# Sh1_MPU.net
KiCad netlist of a schematic drawn in Altium Designer
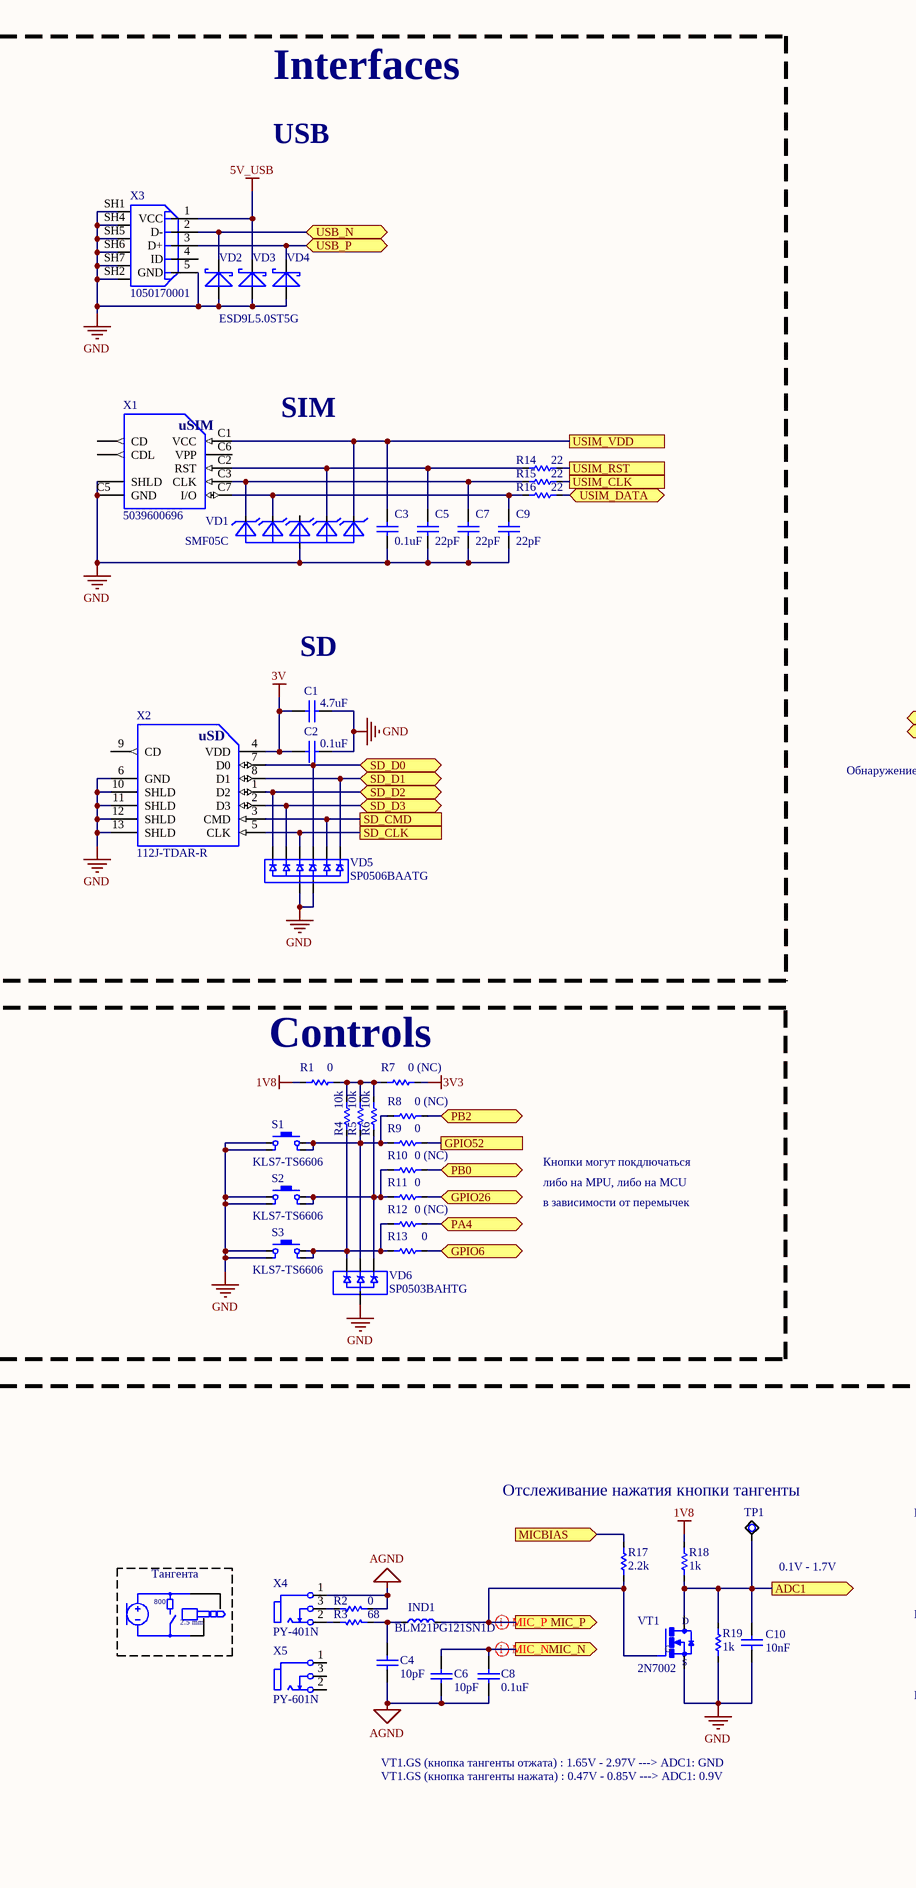
[diagram p0: Sh1_MPU.SchDoc, left]
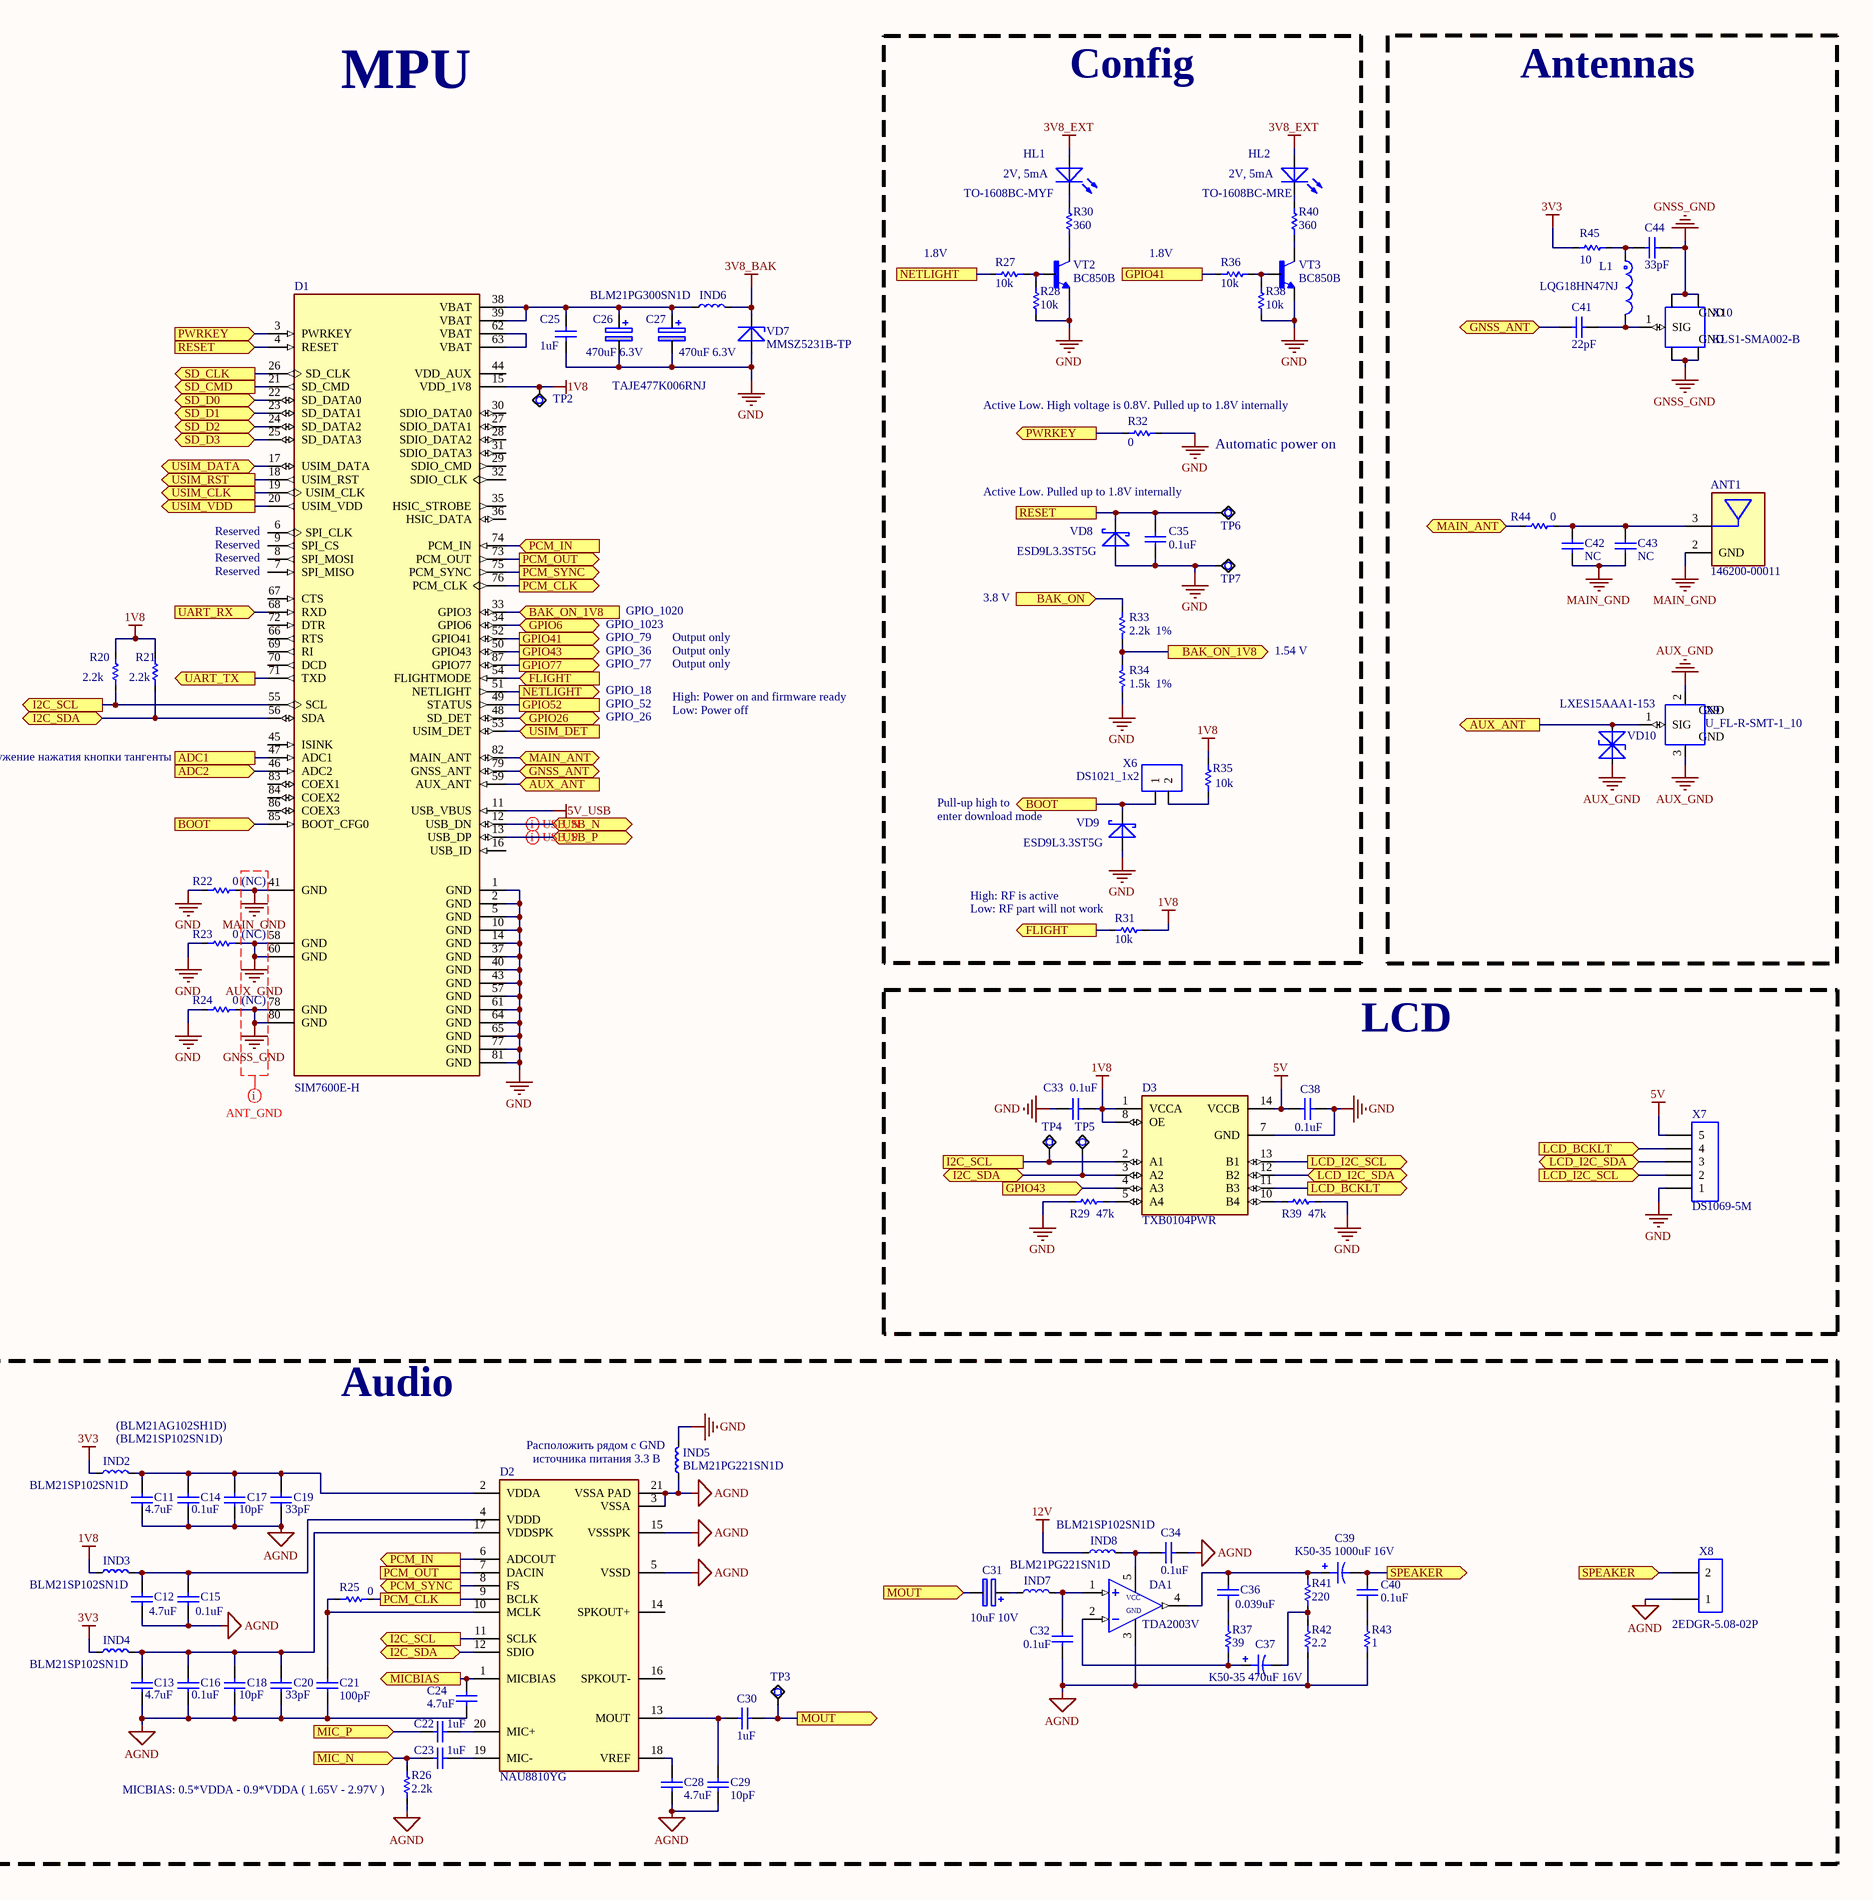
[diagram p1: Sh1_MPU.SchDoc, right]

(export (version "E")
  (design (tool "Eeschema 10.0.6"))
  (components
    (comp (ref "ANT1")
      (value "146200-00011")
      (footprint "Molex_146200-0011_MFG")
      (description "LTE Cellular Ceramic Antenna 698MHz-2.7GHz , SMT")
      (libsource (lib "MyCompLib") (part "146200-0001(11)"))
    )
    (comp (ref "C1")
      (value "4.7uF")
      (footprint "C_SMD0603")
      (description "0603 SMD Capacitor")
      (libsource (lib "") (part "C_SMD_1"))
    )
    (comp (ref "C2")
      (value "0.1uF")
      (footprint "C_SMD0603")
      (description "0603 SMD Capacitor")
      (libsource (lib "") (part "C_SMD_1"))
    )
    (comp (ref "C3")
      (value "0.1uF")
      (footprint "C_SMD0603")
      (description "0603 SMD Capacitor")
      (libsource (lib "") (part "C_SMD_1"))
    )
    (comp (ref "C4")
      (value "10pF")
      (footprint "C_SMD0603")
      (description "0603 SMD Capacitor")
      (libsource (lib "MyCompLib") (part "C_SMD"))
    )
    (comp (ref "C5")
      (value "22pF")
      (footprint "C_SMD0603")
      (description "0603 SMD Capacitor")
      (libsource (lib "") (part "C_SMD_1"))
    )
    (comp (ref "C6")
      (value "10pF")
      (footprint "C_SMD0603")
      (description "0603 SMD Capacitor")
      (libsource (lib "MyCompLib") (part "C_SMD"))
    )
    (comp (ref "C7")
      (value "22pF")
      (footprint "C_SMD0603")
      (description "0603 SMD Capacitor")
      (libsource (lib "") (part "C_SMD_1"))
    )
    (comp (ref "C8")
      (value "0.1uF")
      (footprint "C_SMD0603")
      (description "0603 SMD Capacitor")
      (libsource (lib "MyCompLib") (part "C_SMD"))
    )
    (comp (ref "C9")
      (value "22pF")
      (footprint "C_SMD0603")
      (description "0603 SMD Capacitor")
      (libsource (lib "") (part "C_SMD_1"))
    )
    (comp (ref "C10")
      (value "10nF")
      (footprint "C_SMD0603")
      (description "0603 SMD Capacitor")
      (libsource (lib "MyCompLib") (part "C_SMD"))
    )
    (comp (ref "C11")
      (value "4.7uF")
      (footprint "C_SMD0603")
      (description "0603 SMD Capacitor")
      (libsource (lib "MyCompLib") (part "C_SMD"))
    )
    (comp (ref "C12")
      (value "4.7uF")
      (footprint "C_SMD0603")
      (description "0603 SMD Capacitor")
      (libsource (lib "MyCompLib") (part "C_SMD"))
    )
    (comp (ref "C13")
      (value "4.7uF")
      (footprint "C_SMD0603")
      (description "0603 SMD Capacitor")
      (libsource (lib "MyCompLib") (part "C_SMD"))
    )
    (comp (ref "C14")
      (value "0.1uF")
      (footprint "C_SMD0603")
      (description "0603 SMD Capacitor")
      (libsource (lib "MyCompLib") (part "C_SMD"))
    )
    (comp (ref "C15")
      (value "0.1uF")
      (footprint "C_SMD0603")
      (description "0603 SMD Capacitor")
      (libsource (lib "MyCompLib") (part "C_SMD"))
    )
    (comp (ref "C16")
      (value "0.1uF")
      (footprint "C_SMD0603")
      (description "0603 SMD Capacitor")
      (libsource (lib "MyCompLib") (part "C_SMD"))
    )
    (comp (ref "C17")
      (value "10pF")
      (footprint "C_SMD0603")
      (description "0603 SMD Capacitor")
      (libsource (lib "MyCompLib") (part "C_SMD"))
    )
    (comp (ref "C18")
      (value "10pF")
      (footprint "C_SMD0603")
      (description "0603 SMD Capacitor")
      (libsource (lib "MyCompLib") (part "C_SMD"))
    )
    (comp (ref "C19")
      (value "33pF")
      (footprint "C_SMD0603")
      (description "0603 SMD Capacitor")
      (libsource (lib "MyCompLib") (part "C_SMD"))
    )
    (comp (ref "C20")
      (value "33pF")
      (footprint "C_SMD0603")
      (description "0603 SMD Capacitor")
      (libsource (lib "MyCompLib") (part "C_SMD"))
    )
    (comp (ref "C21")
      (value "100pF")
      (footprint "C_SMD0603")
      (description "0603 SMD Capacitor")
      (libsource (lib "MyCompLib") (part "C_SMD"))
    )
    (comp (ref "C22")
      (value "1uF")
      (footprint "C_SMD0603")
      (description "0603 SMD Capacitor")
      (libsource (lib "MyCompLib") (part "C_SMD"))
    )
    (comp (ref "C23")
      (value "1uF")
      (footprint "C_SMD0603")
      (description "0603 SMD Capacitor")
      (libsource (lib "MyCompLib") (part "C_SMD"))
    )
    (comp (ref "C24")
      (value "4.7uF")
      (footprint "C_SMD0603")
      (description "0603 SMD Capacitor")
      (libsource (lib "MyCompLib") (part "C_SMD"))
    )
    (comp (ref "C25")
      (value "1uF")
      (footprint "C_SMD0603")
      (description "0603 SMD Capacitor")
      (libsource (lib "MyCompLib") (part "C_SMD"))
    )
    (comp (ref "C26")
      (value "470uF 6.3V")
      (footprint "TECAP_E")
      (description "Конденсатор танталовый SMD тип Е")
      (libsource (lib "MyCompLib") (part "C_SMD_Tantalum"))
    )
    (comp (ref "C27")
      (value "470uF 6.3V")
      (footprint "TECAP_E")
      (description "Конденсатор танталовый SMD тип Е")
      (libsource (lib "MyCompLib") (part "C_SMD_Tantalum"))
    )
    (comp (ref "C28")
      (value "4.7uF")
      (footprint "C_SMD0603")
      (description "0603 SMD Capacitor")
      (libsource (lib "MyCompLib") (part "C_SMD"))
    )
    (comp (ref "C29")
      (value "10pF")
      (footprint "C_SMD0603")
      (description "0603 SMD Capacitor")
      (libsource (lib "MyCompLib") (part "C_SMD"))
    )
    (comp (ref "C30")
      (value "1uF")
      (footprint "C_SMD1206")
      (description "1206 SMD Capacitor")
      (libsource (lib "MyCompLib") (part "C_SMD"))
    )
    (comp (ref "C31")
      (value "10uF 10V")
      (footprint "TECAP_B")
      (description "Конденсатор танталовый SMD 10uF 10V тип B")
      (libsource (lib "") (part "C_SMD_Tantalum_1"))
    )
    (comp (ref "C32")
      (value "0.1uF")
      (footprint "C_SMD0603")
      (description "0603 SMD Capacitor")
      (libsource (lib "MyCompLib") (part "C_SMD"))
    )
    (comp (ref "C33")
      (value "0.1uF")
      (footprint "C_SMD0603")
      (description "0603 SMD Capacitor")
      (libsource (lib "MyCompLib") (part "C_SMD"))
    )
    (comp (ref "C34")
      (value "0.1uF")
      (footprint "C_SMD0603")
      (description "0603 SMD Capacitor")
      (libsource (lib "MyCompLib") (part "C_SMD"))
    )
    (comp (ref "C35")
      (value "0.1uF")
      (footprint "C_SMD0603")
      (description "0603 SMD Capacitor")
      (libsource (lib "MyCompLib") (part "C_SMD"))
    )
    (comp (ref "C36")
      (value "0.039uF")
      (footprint "C_SMD0603")
      (description "0603 SMD Capacitor")
      (libsource (lib "MyCompLib") (part "C_SMD"))
    )
    (comp (ref "C37")
      (value "K50-35 470uF 16V")
      (footprint "K50-35 8x11.5x3.5")
      (description "Конденсатор электролитический алюминиевый 470мкФ, 16В")
      (libsource (lib "MyCompLib") (part "K50-35"))
    )
    (comp (ref "C38")
      (value "0.1uF")
      (footprint "C_SMD0603")
      (description "0603 SMD Capacitor")
      (libsource (lib "MyCompLib") (part "C_SMD"))
    )
    (comp (ref "C39")
      (value "K50-35 1000uF 16V")
      (footprint "K50-35 10x12.5x5")
      (description "Конденсатор электролитический алюминиевый 1000мкФ, 16В")
      (libsource (lib "MyCompLib") (part "K50-35"))
    )
    (comp (ref "C40")
      (value "0.1uF")
      (footprint "C_SMD0603")
      (description "0603 SMD Capacitor")
      (libsource (lib "MyCompLib") (part "C_SMD"))
    )
    (comp (ref "C41")
      (value "22pF")
      (footprint "C_SMD0805")
      (description "0805 SMD Capacitor")
      (libsource (lib "MyCompLib") (part "C_SMD"))
    )
    (comp (ref "C42")
      (value "NС")
      (footprint "C_SMD0603")
      (description "0603 SMD Capacitor")
      (libsource (lib "MyCompLib") (part "C_SMD"))
    )
    (comp (ref "C43")
      (value "NС")
      (footprint "C_SMD0603")
      (description "0603 SMD Capacitor")
      (libsource (lib "MyCompLib") (part "C_SMD"))
    )
    (comp (ref "C44")
      (value "33pF")
      (footprint "C_SMD0603")
      (description "0603 SMD Capacitor")
      (libsource (lib "MyCompLib") (part "C_SMD"))
    )
    (comp (ref "D1")
      (value "SIM7600E-H")
      (footprint "IC_SIM7600E-H")
      (description "Multi-Band LTE-TDD/LTE-FDD/HSPA+ and GSM/GPRS/EDGE module")
      (fields (field (name "MF") "Simcom"))
      (libsource (lib "MyCompLib") (part "SIM7600E-H"))
    )
    (comp (ref "D2")
      (value "NAU8810YG")
      (footprint "NAU8810YG")
      (description "AUDIO CODEC MONO 20QFN")
      (fields (field (name "VOLTAGE") "3.6V") (field (name "MANUFACTURER") "Nuvoton Technology Corporation"))
      (libsource (lib "MyCompLib") (part "NAU8810YG"))
    )
    (comp (ref "D3")
      (value "TXB0104PWR")
      (footprint "SOP65P640X120-14N")
      (fields (field (name "MF") "Texas Instruments"))
      (libsource (lib "MyCompLib") (part "TXB0104PWR"))
    )
    (comp (ref "DA1")
      (value "TDA2003V")
      (footprint "TDA2003V _HS-117-30 (ABM-161-30)")
      (description "Amplifier IC 1-Channel _Mono_ Class AB 5-PENTAWATT 10W")
      (fields (field (name "MF") "STMicroelectronics"))
      (libsource (lib "MyCompLib") (part "TDA2003V"))
    )
    (comp (ref "HL1")
      (value "TO-1608BC-MYF")
      (footprint "LED_SMD1608 + THR0254")
      (description "Vf =2 V, 20mA, 0603\r\n\r\nTO-1608BC-BF \\  TO-1608BC-MRE")
      (libsource (lib "MyCompLib") (part "LED_SMD"))
    )
    (comp (ref "HL2")
      (value "TO-1608BC-MRE")
      (footprint "LED_SMD1608 + THR0254")
      (description "Vf =2 V, 20mA, 0603\r\n\r\nTO-1608BC-BF \\  TO-1608BC-MRE")
      (libsource (lib "MyCompLib") (part "LED_SMD"))
    )
    (comp (ref "IND1")
      (value "BLM21PG121SN1D")
      (footprint "BLM21PG221_0805")
      (description "0805, Дроссель подавления ЭМП 120Ohm 25% 100MHz 3A")
      (libsource (lib "") (part "BLM21PG221SN1D_1"))
    )
    (comp (ref "IND2")
      (value "BLM21SP102SN1D")
      (footprint "BLM21PG221_0805")
      (description "0805, Дроссель подавления ЭМП 1KOhm 25% 100MHz 1.6A 0.12Ohm")
      (libsource (lib "MyCompLib") (part "BLM21PG221SN1D"))
    )
    (comp (ref "IND3")
      (value "BLM21SP102SN1D")
      (footprint "BLM21PG221_0805")
      (description "0805, Дроссель подавления ЭМП 1KOhm 25% 100MHz 1.6A 0.12Ohm")
      (libsource (lib "MyCompLib") (part "BLM21PG221SN1D"))
    )
    (comp (ref "IND4")
      (value "BLM21SP102SN1D")
      (footprint "BLM21PG221_0805")
      (description "0805, Дроссель подавления ЭМП 1KOhm 25% 100MHz 1.6A 0.12Ohm")
      (libsource (lib "MyCompLib") (part "BLM21PG221SN1D"))
    )
    (comp (ref "IND5")
      (value "BLM21PG221SN1D")
      (footprint "BLM21PG221_0805")
      (description "0805, Дроссель подавления ЭМП 220Ohm +25% 100MHz 2A 45mOhm")
      (libsource (lib "MyCompLib") (part "BLM21PG221SN1D"))
    )
    (comp (ref "IND6")
      (value "BLM21PG300SN1D")
      (footprint "BLM21PG221_0805")
      (description "0805, Дроссель подавления ЭМП 100МГц:30Ом; 3А")
      (libsource (lib "MyCompLib") (part "BLM21PG221SN1D"))
    )
    (comp (ref "IND7")
      (value "BLM21PG221SN1D")
      (footprint "BLM21PG221_0805")
      (description "0805, Дроссель подавления ЭМП 220Ohm +25% 100MHz 2A 45mOhm")
      (libsource (lib "MyCompLib") (part "BLM21PG221SN1D"))
    )
    (comp (ref "IND8")
      (value "BLM21SP102SN1D")
      (footprint "BLM21PG221_0805")
      (description "0805, Дроссель подавления ЭМП 1KOhm 25% 100MHz 1.6A 0.12Ohm")
      (libsource (lib "MyCompLib") (part "BLM21PG221SN1D"))
    )
    (comp (ref "L1")
      (value "LQG18HN47NJ")
      (footprint "L0603")
      (libsource (lib "MyCompLib") (part "LQG18HN47NJ"))
    )
    (comp (ref "R1")
      (value "0")
      (footprint "R_SMD0603")
      (description "0603 SMD Resistor")
      (libsource (lib "MyCompLib") (part "R_SMD"))
    )
    (comp (ref "R2")
      (value "0")
      (footprint "R_SMD0603")
      (description "0603 SMD Resistor")
      (libsource (lib "MyCompLib") (part "R_SMD"))
    )
    (comp (ref "R3")
      (value "68")
      (footprint "R_SMD0603")
      (description "0603 SMD Resistor")
      (libsource (lib "MyCompLib") (part "R_SMD"))
    )
    (comp (ref "R4")
      (value "10k")
      (footprint "R_SMD0603")
      (description "0603 SMD Resistor")
      (libsource (lib "MyCompLib") (part "R_SMD"))
    )
    (comp (ref "R5")
      (value "10k")
      (footprint "R_SMD0603")
      (description "0603 SMD Resistor")
      (libsource (lib "MyCompLib") (part "R_SMD"))
    )
    (comp (ref "R6")
      (value "10k")
      (footprint "R_SMD0603")
      (description "0603 SMD Resistor")
      (libsource (lib "MyCompLib") (part "R_SMD"))
    )
    (comp (ref "R7")
      (value "0 (NC)")
      (footprint "R_SMD0603")
      (description "0603 SMD Resistor")
      (libsource (lib "MyCompLib") (part "R_SMD"))
    )
    (comp (ref "R8")
      (value "0 (NC)")
      (footprint "R_SMD0603")
      (description "0603 SMD Resistor")
      (libsource (lib "MyCompLib") (part "R_SMD"))
    )
    (comp (ref "R9")
      (value "0")
      (footprint "R_SMD0603")
      (description "0603 SMD Resistor")
      (libsource (lib "MyCompLib") (part "R_SMD"))
    )
    (comp (ref "R10")
      (value "0 (NC)")
      (footprint "R_SMD0603")
      (description "0603 SMD Resistor")
      (libsource (lib "MyCompLib") (part "R_SMD"))
    )
    (comp (ref "R11")
      (value "0")
      (footprint "R_SMD0603")
      (description "0603 SMD Resistor")
      (libsource (lib "MyCompLib") (part "R_SMD"))
    )
    (comp (ref "R12")
      (value "0 (NC)")
      (footprint "R_SMD0603")
      (description "0603 SMD Resistor")
      (libsource (lib "MyCompLib") (part "R_SMD"))
    )
    (comp (ref "R13")
      (value "0")
      (footprint "R_SMD0603")
      (description "0603 SMD Resistor")
      (libsource (lib "MyCompLib") (part "R_SMD"))
    )
    (comp (ref "R14")
      (value "22")
      (footprint "R_SMD0603")
      (description "0603 SMD Resistor")
      (libsource (lib "MyCompLib") (part "R_SMD"))
    )
    (comp (ref "R15")
      (value "22")
      (footprint "R_SMD0603")
      (description "0603 SMD Resistor")
      (libsource (lib "MyCompLib") (part "R_SMD"))
    )
    (comp (ref "R16")
      (value "22")
      (footprint "R_SMD0603")
      (description "0603 SMD Resistor")
      (libsource (lib "MyCompLib") (part "R_SMD"))
    )
    (comp (ref "R17")
      (value "2.2k")
      (footprint "R_SMD0603")
      (description "0603 SMD Resistor")
      (libsource (lib "MyCompLib") (part "R_SMD"))
    )
    (comp (ref "R18")
      (value "1k")
      (footprint "R_SMD0603")
      (description "0603 SMD Resistor")
      (libsource (lib "MyCompLib") (part "R_SMD"))
    )
    (comp (ref "R19")
      (value "1k")
      (footprint "R_SMD0603")
      (description "0603 SMD Resistor")
      (libsource (lib "MyCompLib") (part "R_SMD"))
    )
    (comp (ref "R20")
      (value "2.2k")
      (footprint "R_SMD0603")
      (description "0603 SMD Resistor")
      (libsource (lib "MyCompLib") (part "R_SMD"))
    )
    (comp (ref "R21")
      (value "2.2k")
      (footprint "R_SMD0603")
      (description "0603 SMD Resistor")
      (libsource (lib "MyCompLib") (part "R_SMD"))
    )
    (comp (ref "R22")
      (value "0 (NC)")
      (footprint "R_SMD0805")
      (description "0805 SMD Resistor")
      (libsource (lib "MyCompLib") (part "R_SMD"))
    )
    (comp (ref "R23")
      (value "0 (NC)")
      (footprint "R_SMD0805")
      (description "0805 SMD Resistor")
      (libsource (lib "MyCompLib") (part "R_SMD"))
    )
    (comp (ref "R24")
      (value "0 (NC)")
      (footprint "R_SMD0805")
      (description "0805 SMD Resistor")
      (libsource (lib "MyCompLib") (part "R_SMD"))
    )
    (comp (ref "R25")
      (value "0")
      (footprint "R_SMD0603")
      (description "0603 SMD Resistor")
      (libsource (lib "MyCompLib") (part "R_SMD"))
    )
    (comp (ref "R26")
      (value "2.2k")
      (footprint "R_SMD0603")
      (description "0603 SMD Resistor")
      (libsource (lib "MyCompLib") (part "R_SMD"))
    )
    (comp (ref "R27")
      (value "10k")
      (footprint "R_SMD0603")
      (description "0603 SMD Resistor")
      (libsource (lib "MyCompLib") (part "R_SMD"))
    )
    (comp (ref "R28")
      (value "10k")
      (footprint "R_SMD0603")
      (description "0603 SMD Resistor")
      (libsource (lib "MyCompLib") (part "R_SMD"))
    )
    (comp (ref "R29")
      (value "47k")
      (footprint "R_SMD0603")
      (description "0603 SMD Resistor")
      (libsource (lib "MyCompLib") (part "R_SMD"))
    )
    (comp (ref "R30")
      (value "360")
      (footprint "R_SMD0603")
      (description "0603 SMD Resistor")
      (libsource (lib "MyCompLib") (part "R_SMD"))
    )
    (comp (ref "R31")
      (value "10k")
      (footprint "R_SMD0603")
      (description "0603 SMD Resistor")
      (libsource (lib "MyCompLib") (part "R_SMD"))
    )
    (comp (ref "R32")
      (value "0")
      (footprint "R_SMD0603")
      (description "0603 SMD Resistor")
      (libsource (lib "MyCompLib") (part "R_SMD"))
    )
    (comp (ref "R33")
      (value "2.2k")
      (footprint "R_SMD0603")
      (description "0603 SMD Resistor 1%")
      (libsource (lib "MyCompLib") (part "R_SMD"))
    )
    (comp (ref "R34")
      (value "1.5k")
      (footprint "R_SMD0603")
      (description "0603 SMD Resistor")
      (libsource (lib "MyCompLib") (part "R_SMD"))
    )
    (comp (ref "R35")
      (value "10k")
      (footprint "R_SMD0603")
      (description "0603 SMD Resistor")
      (libsource (lib "MyCompLib") (part "R_SMD"))
    )
    (comp (ref "R36")
      (value "10k")
      (footprint "R_SMD0603")
      (description "0603 SMD Resistor")
      (libsource (lib "MyCompLib") (part "R_SMD"))
    )
    (comp (ref "R37")
      (value "39")
      (footprint "R_SMD0603")
      (description "0603 SMD Resistor")
      (libsource (lib "MyCompLib") (part "R_SMD"))
    )
    (comp (ref "R38")
      (value "10k")
      (footprint "R_SMD0603")
      (description "0603 SMD Resistor")
      (libsource (lib "MyCompLib") (part "R_SMD"))
    )
    (comp (ref "R39")
      (value "47k")
      (footprint "R_SMD0603")
      (description "0603 SMD Resistor")
      (libsource (lib "MyCompLib") (part "R_SMD"))
    )
    (comp (ref "R40")
      (value "360")
      (footprint "R_SMD0603")
      (description "0603 SMD Resistor")
      (libsource (lib "MyCompLib") (part "R_SMD"))
    )
    (comp (ref "R41")
      (value "220")
      (footprint "R_SMD0603")
      (description "0603 SMD Resistor")
      (libsource (lib "MyCompLib") (part "R_SMD"))
    )
    (comp (ref "R42")
      (value "2.2")
      (footprint "R_SMD0603")
      (description "0603 SMD Resistor")
      (libsource (lib "MyCompLib") (part "R_SMD"))
    )
    (comp (ref "R43")
      (value "1")
      (footprint "R_SMD0603")
      (description "0603 SMD Resistor")
      (libsource (lib "MyCompLib") (part "R_SMD"))
    )
    (comp (ref "R44")
      (value "0")
      (footprint "R_SMD0805")
      (description "0805 SMD Resistor")
      (libsource (lib "MyCompLib") (part "R_SMD"))
    )
    (comp (ref "R45")
      (value "10")
      (footprint "R_SMD0603")
      (description "0603 SMD Resistor")
      (libsource (lib "MyCompLib") (part "R_SMD"))
    )
    (comp (ref "S1")
      (value "KLS7-TS6606")
      (footprint "KLS7-TS6606 -7.0")
      (description "6x6 Tact Switch Series")
      (libsource (lib "MyCompLib") (part "KLS7-TS6606-8-180"))
    )
    (comp (ref "S2")
      (value "KLS7-TS6606")
      (footprint "KLS7-TS6606 -7.0")
      (description "6x6 Tact Switch Series")
      (libsource (lib "MyCompLib") (part "KLS7-TS6606-8-180"))
    )
    (comp (ref "S3")
      (value "KLS7-TS6606")
      (footprint "KLS7-TS6606 -7.0")
      (description "6x6 Tact Switch Series")
      (libsource (lib "MyCompLib") (part "KLS7-TS6606-8-180"))
    )
    (comp (ref "TP1")
      (value "Test_point")
      (footprint "TEST_POINT")
      (description "Test point for PCB")
      (libsource (lib "MyCompLib") (part "Test_point"))
    )
    (comp (ref "TP2")
      (value "Test_point")
      (footprint "TEST_POINT")
      (description "Test point for PCB")
      (libsource (lib "MyCompLib") (part "Test_point"))
    )
    (comp (ref "TP3")
      (value "Test_point")
      (footprint "TEST_POINT")
      (description "Test point for PCB")
      (libsource (lib "MyCompLib") (part "Test_point"))
    )
    (comp (ref "TP4")
      (value "Test_point")
      (footprint "TEST_POINT")
      (description "Test point for PCB")
      (libsource (lib "MyCompLib") (part "Test_point"))
    )
    (comp (ref "TP5")
      (value "Test_point")
      (footprint "TEST_POINT")
      (description "Test point for PCB")
      (libsource (lib "MyCompLib") (part "Test_point"))
    )
    (comp (ref "TP6")
      (value "Test_point")
      (footprint "TEST_POINT")
      (description "Test point for PCB")
      (libsource (lib "MyCompLib") (part "Test_point"))
    )
    (comp (ref "TP7")
      (value "Test_point")
      (footprint "TEST_POINT")
      (description "Test point for PCB")
      (libsource (lib "MyCompLib") (part "Test_point"))
    )
    (comp (ref "VD1")
      (value "SMF05C")
      (footprint "SMF05C")
      (description "12.5V Clamp 8A _8/20µs_ Ipp Tvs Diode Surface Mount SC-88/SC70-6/SOT-363")
      (fields (field (name "MF") "ON Semiconductor"))
      (libsource (lib "MyCompLib") (part "SMF05C"))
    )
    (comp (ref "VD2")
      (value "ESD9L5.0ST5G")
      (footprint "ESD9L5_514AB")
      (description "TVS диод защитный 5В_пиковое_рабочее 9.8В_ограничение SOD923")
      (libsource (lib "MyCompLib") (part "ESD9L5.0ST5G"))
    )
    (comp (ref "VD3")
      (value "ESD9L5.0ST5G")
      (footprint "ESD9L5_514AB")
      (description "TVS диод защитный 5В_пиковое_рабочее 9.8В_ограничение SOD923")
      (libsource (lib "MyCompLib") (part "ESD9L5.0ST5G"))
    )
    (comp (ref "VD4")
      (value "ESD9L5.0ST5G")
      (footprint "ESD9L5_514AB")
      (description "TVS диод защитный 5В_пиковое_рабочее 9.8В_ограничение SOD923")
      (libsource (lib "MyCompLib") (part "ESD9L5.0ST5G"))
    )
    (comp (ref "VD5")
      (value "SP0506BAATG")
      (footprint "SOP65P490X110-8N")
      (description "TVS Diode-6 Clamping Voltage Vc Max:8V; MSOP8, Operating Voltage:5.5V;")
      (libsource (lib "MyCompLib") (part "SP0506BAATG"))
    )
    (comp (ref "VD6")
      (value "SP0503BAHTG")
      (footprint "SP0503BAHTG")
      (description "TVS Diode-3 Рабочее напряжение 5.5 В\r\nМаксимальное напряжение фиксации 8.5 в")
      (libsource (lib "MyCompLib") (part "SP0503BAHTG"))
    )
    (comp (ref "VD7")
      (value "MMSZ5231B-TP")
      (footprint "SOD-123_3716X135N")
      (description "Стабилитрон 5.1В, 5%, 0.5Вт, [SOD-123]")
      (libsource (lib "MyCompLib") (part "MMSZ5231B-TP"))
    )
    (comp (ref "VD8")
      (value "ESD9L3.3ST5G")
      (footprint "ESD9L5_514AB")
      (description "TVS диод защитный 5В_пиковое_рабочее 9.8В_ограничение SOD923")
      (libsource (lib "MyCompLib") (part "ESD9L5.0ST5G"))
    )
    (comp (ref "VD9")
      (value "ESD9L3.3ST5G")
      (footprint "ESD9L5_514AB")
      (description "TVS диод защитный 5В_пиковое_рабочее 9.8В_ограничение SOD923")
      (libsource (lib "MyCompLib") (part "ESD9L5.0ST5G"))
    )
    (comp (ref "VD10")
      (value "LXES15AAA1-153")
      (footprint "Murata_LXES15_IPC_A")
      (libsource (lib "MyCompLib") (part "LXES15AAA1-153"))
    )
    (comp (ref "VT1")
      (value "2N7002")
      (footprint "SOT23")
      (description "N-Channel MOSFET 60В 0.115А [SOT-23]")
      (libsource (lib "MyCompLib") (part "2N7002"))
    )
    (comp (ref "VT2")
      (value "BC850B")
      (footprint "SOT23-3")
      (description "Transistor, Npn, 0.1A, 50V, Vbe = 0.7V, hfe = 240 [ SOT23 ]")
      (libsource (lib "MyCompLib") (part "BC850B"))
    )
    (comp (ref "VT3")
      (value "BC850B")
      (footprint "SOT23-3")
      (description "Transistor, Npn, 0.1A, 50V, Vbe = 0.7V, hfe = 240 [ SOT23 ]")
      (libsource (lib "MyCompLib") (part "BC850B"))
    )
    (comp (ref "X1")
      (value "5039600696")
      (footprint "MOLEX_uSIM_5039600696")
      (description "Соединители для карт памяти 1mm microSIM Push Push SMT")
      (libsource (lib "MyCompLib") (part "microSIM_Holder_5039600696"))
    )
    (comp (ref "X2")
      (value "112J-TDAR-R")
      (footprint "112JTDARR")
      (description "Разъем: для карт памяти; SD Micro; push-push; SMT; позолота")
      (libsource (lib "MyCompLib") (part "microSD_112J-TDAR-R"))
    )
    (comp (ref "X3")
      (value "1050170001")
      (footprint "MOLEX_1050170001 - compact")
      (description "USB - micro B USB 2.0 Receptacle Connector 5 Position Surface Mount, Right Angle; Through Hole")
      (fields (field (name "MF") "Molex") (field (name "DIGI-KEY_PART_NUMBER") "WM1399CT-ND"))
      (libsource (lib "MyCompLib") (part "microUSB_1050170001"))
    )
    (comp (ref "X4")
      (value "PY-401N")
      (footprint "PY-401N - compact")
      (description "Гнездо моно 2.5мм")
      (libsource (lib "MyCompLib") (part "microJACK PY-401N"))
    )
    (comp (ref "X5")
      (value "PY-601N")
      (footprint "PY-601N - compact")
      (description "Аудио гнездо (М) 3.5мм")
      (libsource (lib "MyCompLib") (part "miniJACK PY-601N"))
    )
    (comp (ref "X6")
      (value "DS1021_1x2")
      (footprint "PLD2")
      (description "Вилка штыревая 2.54мм 1x2 прямая PLS-2")
      (libsource (lib "MyCompLib") (part "DS1021_1x2"))
    )
    (comp (ref "X7")
      (value "DS1069-5M")
      (footprint "DS1069-5M")
      (description "Вилка Dip прямая\\угловая, шаг 2.50мм Номинальный ток: 3А АС, DC Max")
      (libsource (lib "MyCompLib") (part "DS1069-5M"))
    )
    (comp (ref "X8")
      (value "2EDGR-5.08-02P")
      (footprint "2EDGR-5.08-02P")
      (libsource (lib "MyCompLib") (part "2EDGR-5.08-02P"))
    )
    (comp (ref "X9")
      (value "U_FL-R-SMT-1_10")
      (footprint "HIROSE_0_MFG")
      (libsource (lib "MyCompLib") (part "U_FL-R-SMT-1_10"))
    )
    (comp (ref "X10")
      (value "KLS1-SMA002-B")
      (footprint "SMA-FEMALE-RA - L-KLS1-SMA002-B")
      (description "Разъем угловой SMA гнездо на плату 50 Ом")
      (libsource (lib "MyCompLib") (part "SMA-connector"))
    )
  )
  (nets
    (net (code "1") (name "/ADC1") (class "Default")
      (node (ref "C10") (pin "1") (pinfunction "1_1") (pintype "passive"))
      (node (ref "D1") (pin "47") (pinfunction "ADC1_47") (pintype "input"))
      (node (ref "R18") (pin "2") (pinfunction "CW_2") (pintype "passive"))
      (node (ref "R19") (pin "1") (pinfunction "CCW_1") (pintype "passive"))
      (node (ref "TP1") (pin "1") (pinfunction "1_1") (pintype "passive"))
      (node (ref "VT1") (pin "3") (pinfunction "D_3") (pintype "passive"))
    )
    (net (code "2") (name "/ADC2") (class "Default")
      (node (ref "D1") (pin "46") (pinfunction "ADC2_46") (pintype "input"))
    )
    (net (code "3") (name "/AUX_ANT") (class "Default")
      (node (ref "D1") (pin "59") (pinfunction "AUX_ANT_59") (pintype "input"))
      (node (ref "VD10") (pin "2") (pinfunction "K_2") (pintype "passive"))
      (node (ref "X9") (pin "1") (pinfunction "SIG_1") (pintype "bidirectional"))
    )
    (net (code "4") (name "/BAK_ON") (class "Default")
      (node (ref "R33") (pin "2") (pinfunction "CW_2") (pintype "passive"))
    )
    (net (code "5") (name "/BAK_ON_1V8") (class "Default")
      (node (ref "D1") (pin "33") (pinfunction "GPIO3_33") (pintype "bidirectional"))
      (node (ref "R33") (pin "1") (pinfunction "CCW_1") (pintype "passive"))
      (node (ref "R34") (pin "2") (pinfunction "CW_2") (pintype "passive"))
    )
    (net (code "6") (name "/BOOT") (class "Default")
      (node (ref "D1") (pin "85") (pinfunction "BOOT_CFG0_85") (pintype "input"))
      (node (ref "VD9") (pin "2") (pinfunction "NEG_2") (pintype "passive"))
      (node (ref "X6") (pin "1") (pinfunction "1_1") (pintype "passive"))
    )
    (net (code "7") (name "/FLIGHT") (class "Default")
      (node (ref "D1") (pin "54") (pinfunction "FLIGHTMODE_54") (pintype "input"))
      (node (ref "R31") (pin "1") (pinfunction "CCW_1") (pintype "passive"))
    )
    (net (code "8") (name "/GNSS_ANT") (class "Default")
      (node (ref "C41") (pin "2") (pinfunction "2_2") (pintype "passive"))
      (node (ref "D1") (pin "79") (pinfunction "GNSS_ANT_79") (pintype "bidirectional"))
    )
    (net (code "9") (name "/GPIO6") (class "Default")
      (node (ref "D1") (pin "34") (pinfunction "GPIO6_34") (pintype "bidirectional"))
      (node (ref "R13") (pin "1") (pinfunction "CCW_1") (pintype "passive"))
    )
    (net (code "10") (name "/GPIO26") (class "Default")
      (node (ref "D1") (pin "48") (pinfunction "SD_DET_48") (pintype "bidirectional"))
      (node (ref "R11") (pin "1") (pinfunction "CCW_1") (pintype "passive"))
    )
    (net (code "11") (name "/GPIO41") (class "Default")
      (node (ref "D1") (pin "52") (pinfunction "GPIO41_52") (pintype "bidirectional"))
      (node (ref "R36") (pin "1") (pinfunction "CCW_1") (pintype "passive"))
    )
    (net (code "12") (name "/GPIO43") (class "Default")
      (node (ref "D1") (pin "50") (pinfunction "GPIO43_50") (pintype "bidirectional"))
      (node (ref "D3") (pin "4") (pinfunction "A3_4") (pintype "bidirectional"))
    )
    (net (code "13") (name "/GPIO52") (class "Default")
      (node (ref "D1") (pin "49") (pinfunction "STATUS_49") (pintype "output"))
      (node (ref "R9") (pin "1") (pinfunction "CCW_1") (pintype "passive"))
    )
    (net (code "14") (name "/GPIO77") (class "Default")
      (node (ref "D1") (pin "87") (pinfunction "GPIO77_87") (pintype "bidirectional"))
    )
    (net (code "15") (name "/I2C_SCL") (class "Default")
      (node (ref "D1") (pin "55") (pinfunction "SCL_55") (pintype "output"))
      (node (ref "D2") (pin "11") (pinfunction "SCLK_11") (pintype "passive"))
      (node (ref "D3") (pin "2") (pinfunction "A1_2") (pintype "bidirectional"))
      (node (ref "R20") (pin "1") (pinfunction "CCW_1") (pintype "passive"))
      (node (ref "TP4") (pin "1") (pinfunction "1_1") (pintype "passive"))
    )
    (net (code "16") (name "/I2C_SDA") (class "Default")
      (node (ref "D1") (pin "56") (pinfunction "SDA_56") (pintype "bidirectional"))
      (node (ref "D2") (pin "12") (pinfunction "SDIO_12") (pintype "passive"))
      (node (ref "D3") (pin "3") (pinfunction "A2_3") (pintype "bidirectional"))
      (node (ref "R21") (pin "1") (pinfunction "CCW_1") (pintype "passive"))
      (node (ref "TP5") (pin "1") (pinfunction "1_1") (pintype "passive"))
    )
    (net (code "17") (name "/LCD_BCKLT") (class "Default")
      (node (ref "D3") (pin "11") (pinfunction "B3_11") (pintype "bidirectional"))
      (node (ref "X7") (pin "4") (pinfunction "4_4") (pintype "passive"))
    )
    (net (code "18") (name "/LCD_I2C_SCL") (class "Default")
      (node (ref "D3") (pin "13") (pinfunction "B1_13") (pintype "bidirectional"))
      (node (ref "X7") (pin "2") (pinfunction "2_2") (pintype "passive"))
    )
    (net (code "19") (name "/LCD_I2C_SDA") (class "Default")
      (node (ref "D3") (pin "12") (pinfunction "B2_12") (pintype "bidirectional"))
      (node (ref "X7") (pin "3") (pinfunction "3_3") (pintype "passive"))
    )
    (net (code "20") (name "/MAIN_ANT") (class "Default")
      (node (ref "D1") (pin "82") (pinfunction "MAIN_ANT_82") (pintype "bidirectional"))
      (node (ref "R44") (pin "1") (pinfunction "CCW_1") (pintype "passive"))
    )
    (net (code "21") (name "/MICBIAS") (class "Default")
      (node (ref "C24") (pin "2") (pinfunction "2_2") (pintype "passive"))
      (node (ref "D2") (pin "1") (pinfunction "MICBIAS_1") (pintype "passive"))
      (node (ref "R17") (pin "1") (pinfunction "CCW_1") (pintype "passive"))
    )
    (net (code "22") (name "/MIC_N") (class "Default")
      (node (ref "C23") (pin "1") (pinfunction "1_1") (pintype "passive"))
      (node (ref "C6") (pin "2") (pinfunction "2_2") (pintype "passive"))
      (node (ref "C8") (pin "1") (pinfunction "1_1") (pintype "passive"))
      (node (ref "R26") (pin "1") (pinfunction "CCW_1") (pintype "passive"))
    )
    (net (code "23") (name "/MIC_P") (class "Default")
      (node (ref "C22") (pin "1") (pinfunction "1_1") (pintype "passive"))
      (node (ref "IND1") (pin "1") (pinfunction "1_1") (pintype "passive"))
      (node (ref "R17") (pin "2") (pinfunction "CW_2") (pintype "passive"))
      (node (ref "VT1") (pin "1") (pinfunction "G_1") (pintype "passive"))
    )
    (net (code "24") (name "/MOUT") (class "Default")
      (node (ref "C30") (pin "1") (pinfunction "1_1") (pintype "passive"))
      (node (ref "C31") (pin "2") (pinfunction "-_2") (pintype "passive"))
      (node (ref "TP3") (pin "1") (pinfunction "1_1") (pintype "passive"))
    )
    (net (code "25") (name "/NETLIGHT") (class "Default")
      (node (ref "D1") (pin "51") (pinfunction "NETLIGHT_51") (pintype "output"))
      (node (ref "R27") (pin "1") (pinfunction "CCW_1") (pintype "passive"))
    )
    (net (code "26") (name "/PA4") (class "Default")
      (node (ref "R12") (pin "1") (pinfunction "CCW_1") (pintype "passive"))
    )
    (net (code "27") (name "/PB0") (class "Default")
      (node (ref "R10") (pin "1") (pinfunction "CCW_1") (pintype "passive"))
    )
    (net (code "28") (name "/PB2") (class "Default")
      (node (ref "R8") (pin "1") (pinfunction "CCW_1") (pintype "passive"))
    )
    (net (code "29") (name "/PCM_CLK") (class "Default")
      (node (ref "D1") (pin "76") (pinfunction "PCM_CLK_76") (pintype "output"))
      (node (ref "D2") (pin "9") (pinfunction "BCLK_9") (pintype "passive"))
      (node (ref "R25") (pin "1") (pinfunction "CCW_1") (pintype "passive"))
    )
    (net (code "30") (name "/PCM_IN") (class "Default")
      (node (ref "D1") (pin "74") (pinfunction "PCM_IN_74") (pintype "input"))
      (node (ref "D2") (pin "6") (pinfunction "ADCOUT_6") (pintype "passive"))
    )
    (net (code "31") (name "/PCM_OUT") (class "Default")
      (node (ref "D1") (pin "73") (pinfunction "PCM_OUT_73") (pintype "output"))
      (node (ref "D2") (pin "7") (pinfunction "DACIN_7") (pintype "passive"))
    )
    (net (code "32") (name "/PCM_SYNC") (class "Default")
      (node (ref "D1") (pin "75") (pinfunction "PCM_SYNC_75") (pintype "output"))
      (node (ref "D2") (pin "8") (pinfunction "FS_8") (pintype "passive"))
    )
    (net (code "33") (name "/PWRKEY") (class "Default")
      (node (ref "D1") (pin "3") (pinfunction "PWRKEY_3") (pintype "input"))
      (node (ref "R32") (pin "1") (pinfunction "CCW_1") (pintype "passive"))
    )
    (net (code "34") (name "/RESET") (class "Default")
      (node (ref "C35") (pin "1") (pinfunction "1_1") (pintype "passive"))
      (node (ref "D1") (pin "4") (pinfunction "RESET_4") (pintype "input"))
      (node (ref "TP6") (pin "1") (pinfunction "1_1") (pintype "passive"))
      (node (ref "VD8") (pin "2") (pinfunction "NEG_2") (pintype "passive"))
    )
    (net (code "35") (name "/SD_CLK") (class "Default")
      (node (ref "D1") (pin "26") (pinfunction "SD_CLK_26") (pintype "output"))
      (node (ref "VD5") (pin "4") (pinfunction "B_4") (pintype "passive"))
      (node (ref "X2") (pin "5") (pinfunction "CLK_5") (pintype "input"))
    )
    (net (code "36") (name "/SD_CMD") (class "Default")
      (node (ref "D1") (pin "21") (pinfunction "SD_CMD_21") (pintype "output"))
      (node (ref "VD5") (pin "6") (pinfunction "B_6") (pintype "passive"))
      (node (ref "X2") (pin "3") (pinfunction "CMD_3") (pintype "input"))
    )
    (net (code "37") (name "/SD_D0") (class "Default")
      (node (ref "D1") (pin "22") (pinfunction "SD_DATA0_22") (pintype "bidirectional"))
      (node (ref "VD5") (pin "5") (pinfunction "D_5") (pintype "passive"))
      (node (ref "X2") (pin "7") (pinfunction "D0_7") (pintype "bidirectional"))
    )
    (net (code "38") (name "/SD_D1") (class "Default")
      (node (ref "D1") (pin "23") (pinfunction "SD_DATA1_23") (pintype "bidirectional"))
      (node (ref "VD5") (pin "7") (pinfunction "D_7") (pintype "passive"))
      (node (ref "X2") (pin "8") (pinfunction "D1_8") (pintype "bidirectional"))
    )
    (net (code "39") (name "/SD_D2") (class "Default")
      (node (ref "D1") (pin "24") (pinfunction "SD_DATA2_24") (pintype "bidirectional"))
      (node (ref "VD5") (pin "2") (pinfunction "A_2") (pintype "passive"))
      (node (ref "X2") (pin "1") (pinfunction "D2_1") (pintype "bidirectional"))
    )
    (net (code "40") (name "/SD_D3") (class "Default")
      (node (ref "D1") (pin "25") (pinfunction "SD_DATA3_25") (pintype "bidirectional"))
      (node (ref "VD5") (pin "3") (pinfunction "C_3") (pintype "passive"))
      (node (ref "X2") (pin "2") (pinfunction "D3_2") (pintype "bidirectional"))
    )
    (net (code "41") (name "/SPEAKER") (class "Default")
      (node (ref "C39") (pin "2") (pinfunction "2_2") (pintype "passive"))
      (node (ref "C40") (pin "1") (pinfunction "1_1") (pintype "passive"))
      (node (ref "X8") (pin "2") (pinfunction "2_2") (pintype "passive"))
    )
    (net (code "42") (name "/UART_RX") (class "Default")
      (node (ref "D1") (pin "68") (pinfunction "RXD_68") (pintype "input"))
    )
    (net (code "43") (name "/UART_TX") (class "Default")
      (node (ref "D1") (pin "71") (pinfunction "TXD_71") (pintype "output"))
    )
    (net (code "44") (name "/USB_N") (class "Default")
      (node (ref "D1") (pin "12") (pinfunction "USB_DN_12") (pintype "bidirectional"))
      (node (ref "VD2") (pin "2") (pinfunction "NEG_2") (pintype "passive"))
      (node (ref "X3") (pin "2") (pinfunction "D-_2") (pintype "passive"))
    )
    (net (code "45") (name "/USB_P") (class "Default")
      (node (ref "D1") (pin "13") (pinfunction "USB_DP_13") (pintype "bidirectional"))
      (node (ref "VD4") (pin "2") (pinfunction "NEG_2") (pintype "passive"))
      (node (ref "X3") (pin "3") (pinfunction "D+_3") (pintype "passive"))
    )
    (net (code "46") (name "/USIM_CLK") (class "Default")
      (node (ref "D1") (pin "19") (pinfunction "USIM_CLK_19") (pintype "output"))
      (node (ref "R15") (pin "1") (pinfunction "CCW_1") (pintype "passive"))
    )
    (net (code "47") (name "/USIM_DATA") (class "Default")
      (node (ref "D1") (pin "17") (pinfunction "USIM_DATA_17") (pintype "bidirectional"))
      (node (ref "R16") (pin "1") (pinfunction "CCW_1") (pintype "passive"))
    )
    (net (code "48") (name "/USIM_DET") (class "Default")
      (node (ref "D1") (pin "53") (pinfunction "USIM_DET_53") (pintype "bidirectional"))
    )
    (net (code "49") (name "/USIM_RST") (class "Default")
      (node (ref "D1") (pin "18") (pinfunction "USIM_RST_18") (pintype "output"))
      (node (ref "R14") (pin "1") (pinfunction "CCW_1") (pintype "passive"))
    )
    (net (code "50") (name "/USIM_VDD") (class "Default")
      (node (ref "C3") (pin "1") (pinfunction "1_1") (pintype "passive"))
      (node (ref "D1") (pin "20") (pinfunction "USIM_VDD_20") (pintype "output"))
      (node (ref "VD1") (pin "6") (pinfunction "C5_6") (pintype "passive"))
      (node (ref "X1") (pin "C1") (pinfunction "VCC_C1") (pintype "input"))
    )
    (net (code "51") (name "1V8") (class "Default")
      (node (ref "C33") (pin "1") (pinfunction "1_1") (pintype "passive"))
      (node (ref "D1") (pin "15") (pinfunction "VDD_1V8_15") (pintype "power_in"))
      (node (ref "D3") (pin "1") (pinfunction "VCCA_1") (pintype "power_in"))
      (node (ref "D3") (pin "8") (pinfunction "OE_8") (pintype "bidirectional"))
      (node (ref "IND3") (pin "1") (pinfunction "1_1") (pintype "passive"))
      (node (ref "R1") (pin "2") (pinfunction "CW_2") (pintype "passive"))
      (node (ref "R18") (pin "1") (pinfunction "CCW_1") (pintype "passive"))
      (node (ref "R20") (pin "2") (pinfunction "CW_2") (pintype "passive"))
      (node (ref "R21") (pin "2") (pinfunction "CW_2") (pintype "passive"))
      (node (ref "R31") (pin "2") (pinfunction "CW_2") (pintype "passive"))
      (node (ref "R35") (pin "1") (pinfunction "CCW_1") (pintype "passive"))
      (node (ref "TP2") (pin "1") (pinfunction "1_1") (pintype "passive"))
    )
    (net (code "52") (name "3V") (class "Default")
      (node (ref "C1") (pin "2") (pinfunction "2_2") (pintype "passive"))
      (node (ref "C2") (pin "2") (pinfunction "2_2") (pintype "passive"))
      (node (ref "X2") (pin "4") (pinfunction "VDD_4") (pintype "passive"))
    )
    (net (code "53") (name "3V3") (class "Default")
      (node (ref "IND2") (pin "1") (pinfunction "1_1") (pintype "passive"))
      (node (ref "IND4") (pin "1") (pinfunction "1_1") (pintype "passive"))
      (node (ref "R45") (pin "2") (pinfunction "CW_2") (pintype "passive"))
      (node (ref "R7") (pin "1") (pinfunction "CCW_1") (pintype "passive"))
    )
    (net (code "54") (name "3V8_BAK") (class "Default")
      (node (ref "IND6") (pin "2") (pinfunction "2_2") (pintype "passive"))
      (node (ref "VD7") (pin "C") (pinfunction "NEG_C") (pintype "passive"))
    )
    (net (code "55") (name "3V8_EXT") (class "Default")
      (node (ref "HL1") (pin "1") (pinfunction "POS_1") (pintype "passive"))
      (node (ref "HL2") (pin "1") (pinfunction "POS_1") (pintype "passive"))
    )
    (net (code "56") (name "5V") (class "Default")
      (node (ref "C38") (pin "2") (pinfunction "2_2") (pintype "passive"))
      (node (ref "D3") (pin "14") (pinfunction "VCCB_14") (pintype "power_in"))
      (node (ref "X7") (pin "5") (pinfunction "5_5") (pintype "passive"))
    )
    (net (code "57") (name "5V_USB") (class "Default")
      (node (ref "D1") (pin "11") (pinfunction "USB_VBUS_11") (pintype "input"))
      (node (ref "VD3") (pin "2") (pinfunction "NEG_2") (pintype "passive"))
      (node (ref "X3") (pin "1") (pinfunction "VCC_1") (pintype "power_in"))
    )
    (net (code "58") (name "12V") (class "Default")
      (node (ref "IND8") (pin "1") (pinfunction "1_1") (pintype "passive"))
    )
    (net (code "59") (name "AGND") (class "Default")
      (node (ref "C11") (pin "2") (pinfunction "2_2") (pintype "passive"))
      (node (ref "C12") (pin "2") (pinfunction "2_2") (pintype "passive"))
      (node (ref "C13") (pin "2") (pinfunction "2_2") (pintype "passive"))
      (node (ref "C14") (pin "2") (pinfunction "2_2") (pintype "passive"))
      (node (ref "C15") (pin "2") (pinfunction "2_2") (pintype "passive"))
      (node (ref "C16") (pin "2") (pinfunction "2_2") (pintype "passive"))
      (node (ref "C17") (pin "2") (pinfunction "2_2") (pintype "passive"))
      (node (ref "C18") (pin "2") (pinfunction "2_2") (pintype "passive"))
      (node (ref "C19") (pin "2") (pinfunction "2_2") (pintype "passive"))
      (node (ref "C20") (pin "2") (pinfunction "2_2") (pintype "passive"))
      (node (ref "C21") (pin "1") (pinfunction "1_1") (pintype "passive"))
      (node (ref "C24") (pin "1") (pinfunction "1_1") (pintype "passive"))
      (node (ref "C28") (pin "1") (pinfunction "1_1") (pintype "passive"))
      (node (ref "C29") (pin "1") (pinfunction "1_1") (pintype "passive"))
      (node (ref "C32") (pin "2") (pinfunction "2_2") (pintype "passive"))
      (node (ref "C34") (pin "2") (pinfunction "2_2") (pintype "passive"))
      (node (ref "C4") (pin "2") (pinfunction "2_2") (pintype "passive"))
      (node (ref "C6") (pin "1") (pinfunction "1_1") (pintype "passive"))
      (node (ref "C8") (pin "2") (pinfunction "2_2") (pintype "passive"))
      (node (ref "D2") (pin "15") (pinfunction "VSSSPK_15") (pintype "passive"))
      (node (ref "D2") (pin "21") (pinfunction "VSSA_PAD_21") (pintype "passive"))
      (node (ref "D2") (pin "3") (pinfunction "VSSA_3") (pintype "passive"))
      (node (ref "D2") (pin "5") (pinfunction "VSSD_5") (pintype "passive"))
      (node (ref "DA1") (pin "3") (pinfunction "GND_3") (pintype "power_in"))
      (node (ref "IND5") (pin "1") (pinfunction "1_1") (pintype "passive"))
      (node (ref "R2") (pin "1") (pinfunction "CCW_1") (pintype "passive"))
      (node (ref "R26") (pin "2") (pinfunction "CW_2") (pintype "passive"))
      (node (ref "R42") (pin "2") (pinfunction "CW_2") (pintype "passive"))
      (node (ref "R43") (pin "2") (pinfunction "CW_2") (pintype "passive"))
      (node (ref "X4") (pin "1") (pinfunction "1_1") (pintype "passive"))
      (node (ref "X8") (pin "1") (pinfunction "1_1") (pintype "passive"))
    )
    (net (code "60") (name "AUX_GND") (class "Default")
      (node (ref "D1") (pin "58") (pinfunction "GND_58") (pintype "power_in"))
      (node (ref "D1") (pin "60") (pinfunction "GND_60") (pintype "power_in"))
      (node (ref "R23") (pin "2") (pinfunction "CW_2") (pintype "passive"))
      (node (ref "VD10") (pin "1") (pinfunction "A_1") (pintype "passive"))
      (node (ref "X9") (pin "2") (pinfunction "GND_2") (pintype "power_in"))
      (node (ref "X9") (pin "3") (pinfunction "GND_3") (pintype "power_in"))
    )
    (net (code "61") (name "GND") (class "Default")
      (node (ref "C1") (pin "1") (pinfunction "1_1") (pintype "passive"))
      (node (ref "C10") (pin "2") (pinfunction "2_2") (pintype "passive"))
      (node (ref "C2") (pin "1") (pinfunction "1_1") (pintype "passive"))
      (node (ref "C25") (pin "2") (pinfunction "2_2") (pintype "passive"))
      (node (ref "C26") (pin "2") (pinfunction "-_2") (pintype "passive"))
      (node (ref "C27") (pin "2") (pinfunction "-_2") (pintype "passive"))
      (node (ref "C3") (pin "2") (pinfunction "2_2") (pintype "passive"))
      (node (ref "C33") (pin "2") (pinfunction "2_2") (pintype "passive"))
      (node (ref "C35") (pin "2") (pinfunction "2_2") (pintype "passive"))
      (node (ref "C38") (pin "1") (pinfunction "1_1") (pintype "passive"))
      (node (ref "C5") (pin "2") (pinfunction "2_2") (pintype "passive"))
      (node (ref "C7") (pin "2") (pinfunction "2_2") (pintype "passive"))
      (node (ref "C9") (pin "2") (pinfunction "2_2") (pintype "passive"))
      (node (ref "D1") (pin "1") (pinfunction "GND_1") (pintype "power_in"))
      (node (ref "D1") (pin "10") (pinfunction "GND_10") (pintype "power_in"))
      (node (ref "D1") (pin "14") (pinfunction "GND_14") (pintype "power_in"))
      (node (ref "D1") (pin "2") (pinfunction "GND_2") (pintype "power_in"))
      (node (ref "D1") (pin "37") (pinfunction "GND_37") (pintype "power_in"))
      (node (ref "D1") (pin "40") (pinfunction "GND_40") (pintype "power_in"))
      (node (ref "D1") (pin "43") (pinfunction "GND_43") (pintype "power_in"))
      (node (ref "D1") (pin "5") (pinfunction "GND_5") (pintype "power_in"))
      (node (ref "D1") (pin "57") (pinfunction "GND_57") (pintype "power_in"))
      (node (ref "D1") (pin "61") (pinfunction "GND_61") (pintype "power_in"))
      (node (ref "D1") (pin "64") (pinfunction "GND_64") (pintype "power_in"))
      (node (ref "D1") (pin "65") (pinfunction "GND_65") (pintype "power_in"))
      (node (ref "D1") (pin "77") (pinfunction "GND_77") (pintype "power_in"))
      (node (ref "D1") (pin "81") (pinfunction "GND_81") (pintype "power_in"))
      (node (ref "D3") (pin "7") (pinfunction "GND_7") (pintype "power_in"))
      (node (ref "IND5") (pin "2") (pinfunction "2_2") (pintype "passive"))
      (node (ref "R19") (pin "2") (pinfunction "CW_2") (pintype "passive"))
      (node (ref "R22") (pin "1") (pinfunction "CCW_1") (pintype "passive"))
      (node (ref "R23") (pin "1") (pinfunction "CCW_1") (pintype "passive"))
      (node (ref "R24") (pin "1") (pinfunction "CCW_1") (pintype "passive"))
      (node (ref "R28") (pin "1") (pinfunction "CCW_1") (pintype "passive"))
      (node (ref "R29") (pin "2") (pinfunction "CW_2") (pintype "passive"))
      (node (ref "R32") (pin "2") (pinfunction "CW_2") (pintype "passive"))
      (node (ref "R34") (pin "1") (pinfunction "CCW_1") (pintype "passive"))
      (node (ref "R38") (pin "1") (pinfunction "CCW_1") (pintype "passive"))
      (node (ref "R39") (pin "2") (pinfunction "CW_2") (pintype "passive"))
      (node (ref "S1") (pin "1") (pinfunction "1_1") (pintype "passive"))
      (node (ref "S1") (pin "2") (pinfunction "2_2") (pintype "passive"))
      (node (ref "S2") (pin "1") (pinfunction "1_1") (pintype "passive"))
      (node (ref "S2") (pin "2") (pinfunction "2_2") (pintype "passive"))
      (node (ref "S3") (pin "1") (pinfunction "1_1") (pintype "passive"))
      (node (ref "S3") (pin "2") (pinfunction "2_2") (pintype "passive"))
      (node (ref "TP7") (pin "1") (pinfunction "1_1") (pintype "passive"))
      (node (ref "VD1") (pin "2") (pinfunction "A_2") (pintype "passive"))
      (node (ref "VD2") (pin "1") (pinfunction "POS_1") (pintype "passive"))
      (node (ref "VD3") (pin "1") (pinfunction "POS_1") (pintype "passive"))
      (node (ref "VD4") (pin "1") (pinfunction "POS_1") (pintype "passive"))
      (node (ref "VD5") (pin "1") (pinfunction "GND_1") (pintype "passive"))
      (node (ref "VD5") (pin "8") (pinfunction "GND_8") (pintype "passive"))
      (node (ref "VD6") (pin "1") (pinfunction "GND_1") (pintype "passive"))
      (node (ref "VD7") (pin "A") (pinfunction "POS_A") (pintype "passive"))
      (node (ref "VD8") (pin "1") (pinfunction "POS_1") (pintype "passive"))
      (node (ref "VD9") (pin "1") (pinfunction "POS_1") (pintype "passive"))
      (node (ref "VT1") (pin "2") (pinfunction "S_2") (pintype "passive"))
      (node (ref "VT2") (pin "2") (pinfunction "E_2") (pintype "passive"))
      (node (ref "VT3") (pin "2") (pinfunction "E_2") (pintype "passive"))
      (node (ref "X1") (pin "C5") (pinfunction "GND_C5") (pintype "passive"))
      (node (ref "X1") (pin "SHLD") (pinfunction "SHLD_SHLD") (pintype "passive"))
      (node (ref "X2") (pin "10") (pinfunction "SHLD_10") (pintype "passive"))
      (node (ref "X2") (pin "11") (pinfunction "SHLD_11") (pintype "passive"))
      (node (ref "X2") (pin "12") (pinfunction "SHLD_12") (pintype "passive"))
      (node (ref "X2") (pin "13") (pinfunction "SHLD_13") (pintype "passive"))
      (node (ref "X2") (pin "6") (pinfunction "GND_6") (pintype "passive"))
      (node (ref "X3") (pin "5") (pinfunction "GND_5") (pintype "power_in"))
      (node (ref "X3") (pin "SH1") (pinfunction "SHIELD_SH1") (pintype "passive"))
      (node (ref "X3") (pin "SH2") (pinfunction "SHIELD_SH2") (pintype "passive"))
      (node (ref "X3") (pin "SH4") (pinfunction "SHIELD_SH4") (pintype "passive"))
      (node (ref "X3") (pin "SH5") (pinfunction "SHIELD_SH5") (pintype "passive"))
      (node (ref "X3") (pin "SH6") (pinfunction "SHIELD_SH6") (pintype "passive"))
      (node (ref "X3") (pin "SH7") (pinfunction "SHIELD_SH7") (pintype "passive"))
      (node (ref "X7") (pin "1") (pinfunction "1_1") (pintype "passive"))
    )
    (net (code "62") (name "GNSS_GND") (class "Default")
      (node (ref "C44") (pin "1") (pinfunction "1_1") (pintype "passive"))
      (node (ref "D1") (pin "78") (pinfunction "GND_78") (pintype "power_in"))
      (node (ref "D1") (pin "80") (pinfunction "GND_80") (pintype "power_in"))
      (node (ref "R24") (pin "2") (pinfunction "CW_2") (pintype "passive"))
      (node (ref "X10") (pin "G") (pinfunction "GND_G") (pintype "power_in"))
    )
    (net (code "63") (name "MAIN_GND") (class "Default")
      (node (ref "ANT1") (pin "2") (pinfunction "GND_2") (pintype "power_in"))
      (node (ref "C42") (pin "1") (pinfunction "1_1") (pintype "passive"))
      (node (ref "C43") (pin "1") (pinfunction "1_1") (pintype "passive"))
      (node (ref "D1") (pin "41") (pinfunction "GND_41") (pintype "power_in"))
      (node (ref "R22") (pin "2") (pinfunction "CW_2") (pintype "passive"))
    )
    (net (code "64") (name "Net-(ANT1-FEEDING)") (class "Default")
      (node (ref "ANT1") (pin "3") (pinfunction "FEEDING_3") (pintype "passive"))
      (node (ref "C42") (pin "2") (pinfunction "2_2") (pintype "passive"))
      (node (ref "C43") (pin "2") (pinfunction "2_2") (pintype "passive"))
      (node (ref "R44") (pin "2") (pinfunction "CW_2") (pintype "passive"))
    )
    (net (code "65") (name "Net-(C26-+)") (class "Default")
      (node (ref "C25") (pin "1") (pinfunction "1_1") (pintype "passive"))
      (node (ref "C26") (pin "1") (pinfunction "+_1") (pintype "passive"))
      (node (ref "C27") (pin "1") (pinfunction "+_1") (pintype "passive"))
      (node (ref "D1") (pin "38") (pinfunction "VBAT_38") (pintype "power_in"))
      (node (ref "D1") (pin "39") (pinfunction "VBAT_39") (pintype "power_in"))
      (node (ref "IND6") (pin "1") (pinfunction "1_1") (pintype "passive"))
    )
    (net (code "66") (name "Net-(C31-+)") (class "Default")
      (node (ref "C31") (pin "1") (pinfunction "+_1") (pintype "passive"))
      (node (ref "IND7") (pin "1") (pinfunction "1_1") (pintype "passive"))
    )
    (net (code "67") (name "Net-(D1-VBAT-Pad62)") (class "Default")
      (node (ref "D1") (pin "62") (pinfunction "VBAT_62") (pintype "power_in"))
      (node (ref "D1") (pin "63") (pinfunction "VBAT_63") (pintype "power_in"))
    )
    (net (code "68") (name "Net-(D2-MCLK)") (class "Default")
      (node (ref "C21") (pin "2") (pinfunction "2_2") (pintype "passive"))
      (node (ref "D2") (pin "10") (pinfunction "MCLK_10") (pintype "passive"))
      (node (ref "R25") (pin "2") (pinfunction "CW_2") (pintype "passive"))
    )
    (net (code "69") (name "Net-(D2-MIC+)") (class "Default")
      (node (ref "C22") (pin "2") (pinfunction "2_2") (pintype "passive"))
      (node (ref "D2") (pin "20") (pinfunction "MIC+_20") (pintype "passive"))
    )
    (net (code "70") (name "Net-(D2-MIC-)") (class "Default")
      (node (ref "C23") (pin "2") (pinfunction "2_2") (pintype "passive"))
      (node (ref "D2") (pin "19") (pinfunction "MIC-_19") (pintype "passive"))
    )
    (net (code "71") (name "Net-(D2-MOUT)") (class "Default")
      (node (ref "C29") (pin "2") (pinfunction "2_2") (pintype "passive"))
      (node (ref "C30") (pin "2") (pinfunction "2_2") (pintype "passive"))
      (node (ref "D2") (pin "13") (pinfunction "MOUT_13") (pintype "passive"))
    )
    (net (code "72") (name "Net-(D2-VDDA)") (class "Default")
      (node (ref "C11") (pin "1") (pinfunction "1_1") (pintype "passive"))
      (node (ref "C14") (pin "1") (pinfunction "1_1") (pintype "passive"))
      (node (ref "C17") (pin "1") (pinfunction "1_1") (pintype "passive"))
      (node (ref "C19") (pin "1") (pinfunction "1_1") (pintype "passive"))
      (node (ref "D2") (pin "2") (pinfunction "VDDA_2") (pintype "passive"))
      (node (ref "IND2") (pin "2") (pinfunction "2_2") (pintype "passive"))
    )
    (net (code "73") (name "Net-(D2-VDDD)") (class "Default")
      (node (ref "C12") (pin "1") (pinfunction "1_1") (pintype "passive"))
      (node (ref "C15") (pin "1") (pinfunction "1_1") (pintype "passive"))
      (node (ref "D2") (pin "4") (pinfunction "VDDD_4") (pintype "passive"))
      (node (ref "IND3") (pin "2") (pinfunction "2_2") (pintype "passive"))
    )
    (net (code "74") (name "Net-(D2-VDDSPK)") (class "Default")
      (node (ref "C13") (pin "1") (pinfunction "1_1") (pintype "passive"))
      (node (ref "C16") (pin "1") (pinfunction "1_1") (pintype "passive"))
      (node (ref "C18") (pin "1") (pinfunction "1_1") (pintype "passive"))
      (node (ref "C20") (pin "1") (pinfunction "1_1") (pintype "passive"))
      (node (ref "D2") (pin "17") (pinfunction "VDDSPK_17") (pintype "passive"))
      (node (ref "IND4") (pin "2") (pinfunction "2_2") (pintype "passive"))
    )
    (net (code "75") (name "Net-(D2-VREF)") (class "Default")
      (node (ref "C28") (pin "2") (pinfunction "2_2") (pintype "passive"))
      (node (ref "D2") (pin "18") (pinfunction "VREF_18") (pintype "passive"))
    )
    (net (code "76") (name "Net-(D3-A4)") (class "Default")
      (node (ref "D3") (pin "5") (pinfunction "A4_5") (pintype "bidirectional"))
      (node (ref "R29") (pin "1") (pinfunction "CCW_1") (pintype "passive"))
    )
    (net (code "77") (name "Net-(D3-B4)") (class "Default")
      (node (ref "D3") (pin "10") (pinfunction "B4_10") (pintype "bidirectional"))
      (node (ref "R39") (pin "1") (pinfunction "CCW_1") (pintype "passive"))
    )
    (net (code "78") (name "Net-(DA1-+IN)") (class "Default")
      (node (ref "C32") (pin "1") (pinfunction "1_1") (pintype "passive"))
      (node (ref "DA1") (pin "1") (pinfunction "+IN_1") (pintype "input"))
      (node (ref "IND7") (pin "2") (pinfunction "2_2") (pintype "passive"))
    )
    (net (code "79") (name "Net-(DA1--IN)") (class "Default")
      (node (ref "C37") (pin "1") (pinfunction "1_1") (pintype "passive"))
      (node (ref "DA1") (pin "2") (pinfunction "-IN_2") (pintype "input"))
      (node (ref "R37") (pin "2") (pinfunction "CW_2") (pintype "passive"))
    )
    (net (code "80") (name "Net-(DA1-OUT)") (class "Default")
      (node (ref "C36") (pin "1") (pinfunction "1_1") (pintype "passive"))
      (node (ref "C39") (pin "1") (pinfunction "1_1") (pintype "passive"))
      (node (ref "DA1") (pin "4") (pinfunction "OUT_4") (pintype "output"))
      (node (ref "R41") (pin "1") (pinfunction "CCW_1") (pintype "passive"))
    )
    (net (code "81") (name "Net-(DA1-VCC)") (class "Default")
      (node (ref "C34") (pin "1") (pinfunction "1_1") (pintype "passive"))
      (node (ref "DA1") (pin "5") (pinfunction "VCC_5") (pintype "power_in"))
      (node (ref "IND8") (pin "2") (pinfunction "2_2") (pintype "passive"))
    )
    (net (code "82") (name "Net-(HL1-NEG)") (class "Default")
      (node (ref "HL1") (pin "2") (pinfunction "NEG_2") (pintype "passive"))
      (node (ref "R30") (pin "2") (pinfunction "CW_2") (pintype "passive"))
    )
    (net (code "83") (name "Net-(HL2-NEG)") (class "Default")
      (node (ref "HL2") (pin "2") (pinfunction "NEG_2") (pintype "passive"))
      (node (ref "R40") (pin "2") (pinfunction "CW_2") (pintype "passive"))
    )
    (net (code "84") (name "Net-(R1-CCW)") (class "Default")
      (node (ref "R1") (pin "1") (pinfunction "CCW_1") (pintype "passive"))
      (node (ref "R4") (pin "2") (pinfunction "CW_2") (pintype "passive"))
      (node (ref "R5") (pin "2") (pinfunction "CW_2") (pintype "passive"))
      (node (ref "R6") (pin "2") (pinfunction "CW_2") (pintype "passive"))
      (node (ref "R7") (pin "2") (pinfunction "CW_2") (pintype "passive"))
    )
    (net (code "85") (name "Net-(R2-CW)") (class "Default")
      (node (ref "R2") (pin "2") (pinfunction "CW_2") (pintype "passive"))
      (node (ref "X4") (pin "3") (pinfunction "3_3") (pintype "passive"))
    )
    (net (code "86") (name "Net-(R3-CCW)") (class "Default")
      (node (ref "C4") (pin "1") (pinfunction "1_1") (pintype "passive"))
      (node (ref "IND1") (pin "2") (pinfunction "2_2") (pintype "passive"))
      (node (ref "R3") (pin "1") (pinfunction "CCW_1") (pintype "passive"))
    )
    (net (code "87") (name "Net-(R3-CW)") (class "Default")
      (node (ref "R3") (pin "2") (pinfunction "CW_2") (pintype "passive"))
      (node (ref "X4") (pin "2") (pinfunction "2_2") (pintype "passive"))
    )
    (net (code "88") (name "Net-(R5-CCW)") (class "Default")
      (node (ref "R5") (pin "1") (pinfunction "CCW_1") (pintype "passive"))
      (node (ref "R8") (pin "2") (pinfunction "CW_2") (pintype "passive"))
      (node (ref "R9") (pin "2") (pinfunction "CW_2") (pintype "passive"))
      (node (ref "S1") (pin "3") (pinfunction "3_3") (pintype "passive"))
      (node (ref "S1") (pin "4") (pinfunction "4_4") (pintype "passive"))
      (node (ref "VD6") (pin "4") (pinfunction "C_4") (pintype "passive"))
    )
    (net (code "89") (name "Net-(R10-CW)") (class "Default")
      (node (ref "R10") (pin "2") (pinfunction "CW_2") (pintype "passive"))
      (node (ref "R11") (pin "2") (pinfunction "CW_2") (pintype "passive"))
      (node (ref "R6") (pin "1") (pinfunction "CCW_1") (pintype "passive"))
      (node (ref "S2") (pin "3") (pinfunction "3_3") (pintype "passive"))
      (node (ref "S2") (pin "4") (pinfunction "4_4") (pintype "passive"))
      (node (ref "VD6") (pin "3") (pinfunction "B_3") (pintype "passive"))
    )
    (net (code "90") (name "Net-(R12-CW)") (class "Default")
      (node (ref "R12") (pin "2") (pinfunction "CW_2") (pintype "passive"))
      (node (ref "R13") (pin "2") (pinfunction "CW_2") (pintype "passive"))
      (node (ref "R4") (pin "1") (pinfunction "CCW_1") (pintype "passive"))
      (node (ref "S3") (pin "3") (pinfunction "3_3") (pintype "passive"))
      (node (ref "S3") (pin "4") (pinfunction "4_4") (pintype "passive"))
      (node (ref "VD6") (pin "2") (pinfunction "A_2") (pintype "passive"))
    )
    (net (code "91") (name "Net-(R14-CW)") (class "Default")
      (node (ref "C5") (pin "1") (pinfunction "1_1") (pintype "passive"))
      (node (ref "R14") (pin "2") (pinfunction "CW_2") (pintype "passive"))
      (node (ref "VD1") (pin "5") (pinfunction "C4_5") (pintype "passive"))
      (node (ref "X1") (pin "C2") (pinfunction "RST_C2") (pintype "input"))
    )
    (net (code "92") (name "Net-(R15-CW)") (class "Default")
      (node (ref "C7") (pin "1") (pinfunction "1_1") (pintype "passive"))
      (node (ref "R15") (pin "2") (pinfunction "CW_2") (pintype "passive"))
      (node (ref "VD1") (pin "1") (pinfunction "C1_1") (pintype "passive"))
      (node (ref "X1") (pin "C3") (pinfunction "CLK_C3") (pintype "input"))
    )
    (net (code "93") (name "Net-(R16-CW)") (class "Default")
      (node (ref "C9") (pin "1") (pinfunction "1_1") (pintype "passive"))
      (node (ref "R16") (pin "2") (pinfunction "CW_2") (pintype "passive"))
      (node (ref "VD1") (pin "3") (pinfunction "C2_3") (pintype "passive"))
      (node (ref "X1") (pin "C7") (pinfunction "I/O_C7") (pintype "bidirectional"))
    )
    (net (code "94") (name "Net-(R27-CW)") (class "Default")
      (node (ref "R27") (pin "2") (pinfunction "CW_2") (pintype "passive"))
      (node (ref "R28") (pin "2") (pinfunction "CW_2") (pintype "passive"))
      (node (ref "VT2") (pin "1") (pinfunction "B_1") (pintype "passive"))
    )
    (net (code "95") (name "Net-(R30-CCW)") (class "Default")
      (node (ref "R30") (pin "1") (pinfunction "CCW_1") (pintype "passive"))
      (node (ref "VT2") (pin "3") (pinfunction "C_3") (pintype "passive"))
    )
    (net (code "96") (name "Net-(R35-CW)") (class "Default")
      (node (ref "R35") (pin "2") (pinfunction "CW_2") (pintype "passive"))
      (node (ref "X6") (pin "2") (pinfunction "2_2") (pintype "passive"))
    )
    (net (code "97") (name "Net-(R36-CW)") (class "Default")
      (node (ref "R36") (pin "2") (pinfunction "CW_2") (pintype "passive"))
      (node (ref "R38") (pin "2") (pinfunction "CW_2") (pintype "passive"))
      (node (ref "VT3") (pin "1") (pinfunction "B_1") (pintype "passive"))
    )
    (net (code "98") (name "Net-(R37-CCW)") (class "Default")
      (node (ref "C36") (pin "2") (pinfunction "2_2") (pintype "passive"))
      (node (ref "R37") (pin "1") (pinfunction "CCW_1") (pintype "passive"))
    )
    (net (code "99") (name "Net-(R40-CCW)") (class "Default")
      (node (ref "R40") (pin "1") (pinfunction "CCW_1") (pintype "passive"))
      (node (ref "VT3") (pin "3") (pinfunction "C_3") (pintype "passive"))
    )
    (net (code "100") (name "Net-(R41-CW)") (class "Default")
      (node (ref "C37") (pin "2") (pinfunction "2_2") (pintype "passive"))
      (node (ref "R41") (pin "2") (pinfunction "CW_2") (pintype "passive"))
      (node (ref "R42") (pin "1") (pinfunction "CCW_1") (pintype "passive"))
    )
    (net (code "101") (name "Net-(R43-CCW)") (class "Default")
      (node (ref "C40") (pin "2") (pinfunction "2_2") (pintype "passive"))
      (node (ref "R43") (pin "1") (pinfunction "CCW_1") (pintype "passive"))
    )
    (net (code "102") (name "Net-(R45-CCW)") (class "Default")
      (node (ref "C44") (pin "2") (pinfunction "2_2") (pintype "passive"))
      (node (ref "L1") (pin "1") (pinfunction "1_1") (pintype "passive"))
      (node (ref "R45") (pin "1") (pinfunction "CCW_1") (pintype "passive"))
    )
    (net (code "103") (name "Net-(X10-SIG)") (class "Default")
      (node (ref "C41") (pin "1") (pinfunction "1_1") (pintype "passive"))
      (node (ref "L1") (pin "2") (pinfunction "2_2") (pintype "passive"))
      (node (ref "X10") (pin "1") (pinfunction "SIG_1") (pintype "bidirectional"))
    )
    (net (code "104") (name "unconnected-(D1-COEX1-Pad83)") (class "Default")
      (node (ref "D1") (pin "83") (pinfunction "COEX1_83") (pintype "bidirectional"))
    )
    (net (code "105") (name "unconnected-(D1-COEX2-Pad84)") (class "Default")
      (node (ref "D1") (pin "84") (pinfunction "COEX2_84") (pintype "bidirectional"))
    )
    (net (code "106") (name "unconnected-(D1-COEX3-Pad86)") (class "Default")
      (node (ref "D1") (pin "86") (pinfunction "COEX3_86") (pintype "bidirectional"))
    )
    (net (code "107") (name "unconnected-(D1-CTS-Pad67)") (class "Default")
      (node (ref "D1") (pin "67") (pinfunction "CTS_67") (pintype "input"))
    )
    (net (code "108") (name "unconnected-(D1-DCD-Pad70)") (class "Default")
      (node (ref "D1") (pin "70") (pinfunction "DCD_70") (pintype "output"))
    )
    (net (code "109") (name "unconnected-(D1-DTR-Pad72)") (class "Default")
      (node (ref "D1") (pin "72") (pinfunction "DTR_72") (pintype "input"))
    )
    (net (code "110") (name "unconnected-(D1-HSIC_DATA-Pad36)") (class "Default")
      (node (ref "D1") (pin "36") (pinfunction "HSIC_DATA_36") (pintype "bidirectional"))
    )
    (net (code "111") (name "unconnected-(D1-HSIC_STROBE-Pad35)") (class "Default")
      (node (ref "D1") (pin "35") (pinfunction "HSIC_STROBE_35") (pintype "output"))
    )
    (net (code "112") (name "unconnected-(D1-ISINK-Pad45)") (class "Default")
      (node (ref "D1") (pin "45") (pinfunction "ISINK_45") (pintype "input"))
    )
    (net (code "113") (name "unconnected-(D1-RI-Pad69)") (class "Default")
      (node (ref "D1") (pin "69") (pinfunction "RI_69") (pintype "output"))
    )
    (net (code "114") (name "unconnected-(D1-RTS-Pad66)") (class "Default")
      (node (ref "D1") (pin "66") (pinfunction "RTS_66") (pintype "output"))
    )
    (net (code "115") (name "unconnected-(D1-SDIO_CLK-Pad32)") (class "Default")
      (node (ref "D1") (pin "32") (pinfunction "SDIO_CLK_32") (pintype "output"))
    )
    (net (code "116") (name "unconnected-(D1-SDIO_CMD-Pad29)") (class "Default")
      (node (ref "D1") (pin "29") (pinfunction "SDIO_CMD_29") (pintype "output"))
    )
    (net (code "117") (name "unconnected-(D1-SDIO_DATA0-Pad30)") (class "Default")
      (node (ref "D1") (pin "30") (pinfunction "SDIO_DATA0_30") (pintype "bidirectional"))
    )
    (net (code "118") (name "unconnected-(D1-SDIO_DATA1-Pad27)") (class "Default")
      (node (ref "D1") (pin "27") (pinfunction "SDIO_DATA1_27") (pintype "bidirectional"))
    )
    (net (code "119") (name "unconnected-(D1-SDIO_DATA2-Pad28)") (class "Default")
      (node (ref "D1") (pin "28") (pinfunction "SDIO_DATA2_28") (pintype "bidirectional"))
    )
    (net (code "120") (name "unconnected-(D1-SDIO_DATA3-Pad31)") (class "Default")
      (node (ref "D1") (pin "31") (pinfunction "SDIO_DATA3_31") (pintype "bidirectional"))
    )
    (net (code "121") (name "unconnected-(D1-SPI_CLK-Pad6)") (class "Default")
      (node (ref "D1") (pin "6") (pinfunction "SPI_CLK_6") (pintype "output"))
    )
    (net (code "122") (name "unconnected-(D1-SPI_CS-Pad9)") (class "Default")
      (node (ref "D1") (pin "9") (pinfunction "SPI_CS_9") (pintype "output"))
    )
    (net (code "123") (name "unconnected-(D1-SPI_MISO-Pad7)") (class "Default")
      (node (ref "D1") (pin "7") (pinfunction "SPI_MISO_7") (pintype "input"))
    )
    (net (code "124") (name "unconnected-(D1-SPI_MOSI-Pad8)") (class "Default")
      (node (ref "D1") (pin "8") (pinfunction "SPI_MOSI_8") (pintype "output"))
    )
    (net (code "125") (name "unconnected-(D1-USB_ID-Pad16)") (class "Default")
      (node (ref "D1") (pin "16") (pinfunction "USB_ID_16") (pintype "input"))
    )
    (net (code "126") (name "unconnected-(D1-VDD_AUX-Pad44)") (class "Default")
      (node (ref "D1") (pin "44") (pinfunction "VDD_AUX_44") (pintype "power_in"))
    )
    (net (code "127") (name "unconnected-(D2-SPKOUT+-Pad14)") (class "Default")
      (node (ref "D2") (pin "14") (pinfunction "SPKOUT+_14") (pintype "passive"))
    )
    (net (code "128") (name "unconnected-(D2-SPKOUT--Pad16)") (class "Default")
      (node (ref "D2") (pin "16") (pinfunction "SPKOUT-_16") (pintype "passive"))
    )
    (net (code "129") (name "unconnected-(VD1-C3-Pad4)") (class "Default")
      (node (ref "VD1") (pin "4") (pinfunction "C3_4") (pintype "passive"))
    )
    (net (code "130") (name "unconnected-(X1-PadCD)") (class "Default")
      (node (ref "X1") (pin "CD") (pinfunction "CD_CD") (pintype "output"))
    )
    (net (code "131") (name "unconnected-(X1-PadCDL)") (class "Default")
      (node (ref "X1") (pin "CDL") (pinfunction "CDL_CDL") (pintype "output"))
    )
    (net (code "132") (name "unconnected-(X1-VPP-PadC6)") (class "Default")
      (node (ref "X1") (pin "C6") (pinfunction "VPP_C6") (pintype "passive"))
    )
    (net (code "133") (name "unconnected-(X2-CD-Pad9)") (class "Default")
      (node (ref "X2") (pin "9") (pinfunction "CD_9") (pintype "output"))
    )
    (net (code "134") (name "unconnected-(X3-ID-Pad4)") (class "Default")
      (node (ref "X3") (pin "4") (pinfunction "ID_4") (pintype "passive"))
    )
    (net (code "135") (name "unconnected-(X5-Pad1)") (class "Default")
      (node (ref "X5") (pin "1") (pinfunction "1_1") (pintype "passive"))
    )
    (net (code "136") (name "unconnected-(X5-Pad2)") (class "Default")
      (node (ref "X5") (pin "2") (pinfunction "2_2") (pintype "passive"))
    )
    (net (code "137") (name "unconnected-(X5-Pad3)") (class "Default")
      (node (ref "X5") (pin "3") (pinfunction "3_3") (pintype "passive"))
    )
  )
)
